# smarty09b.net
KiCad netlist of a schematic drawn in EAGLE
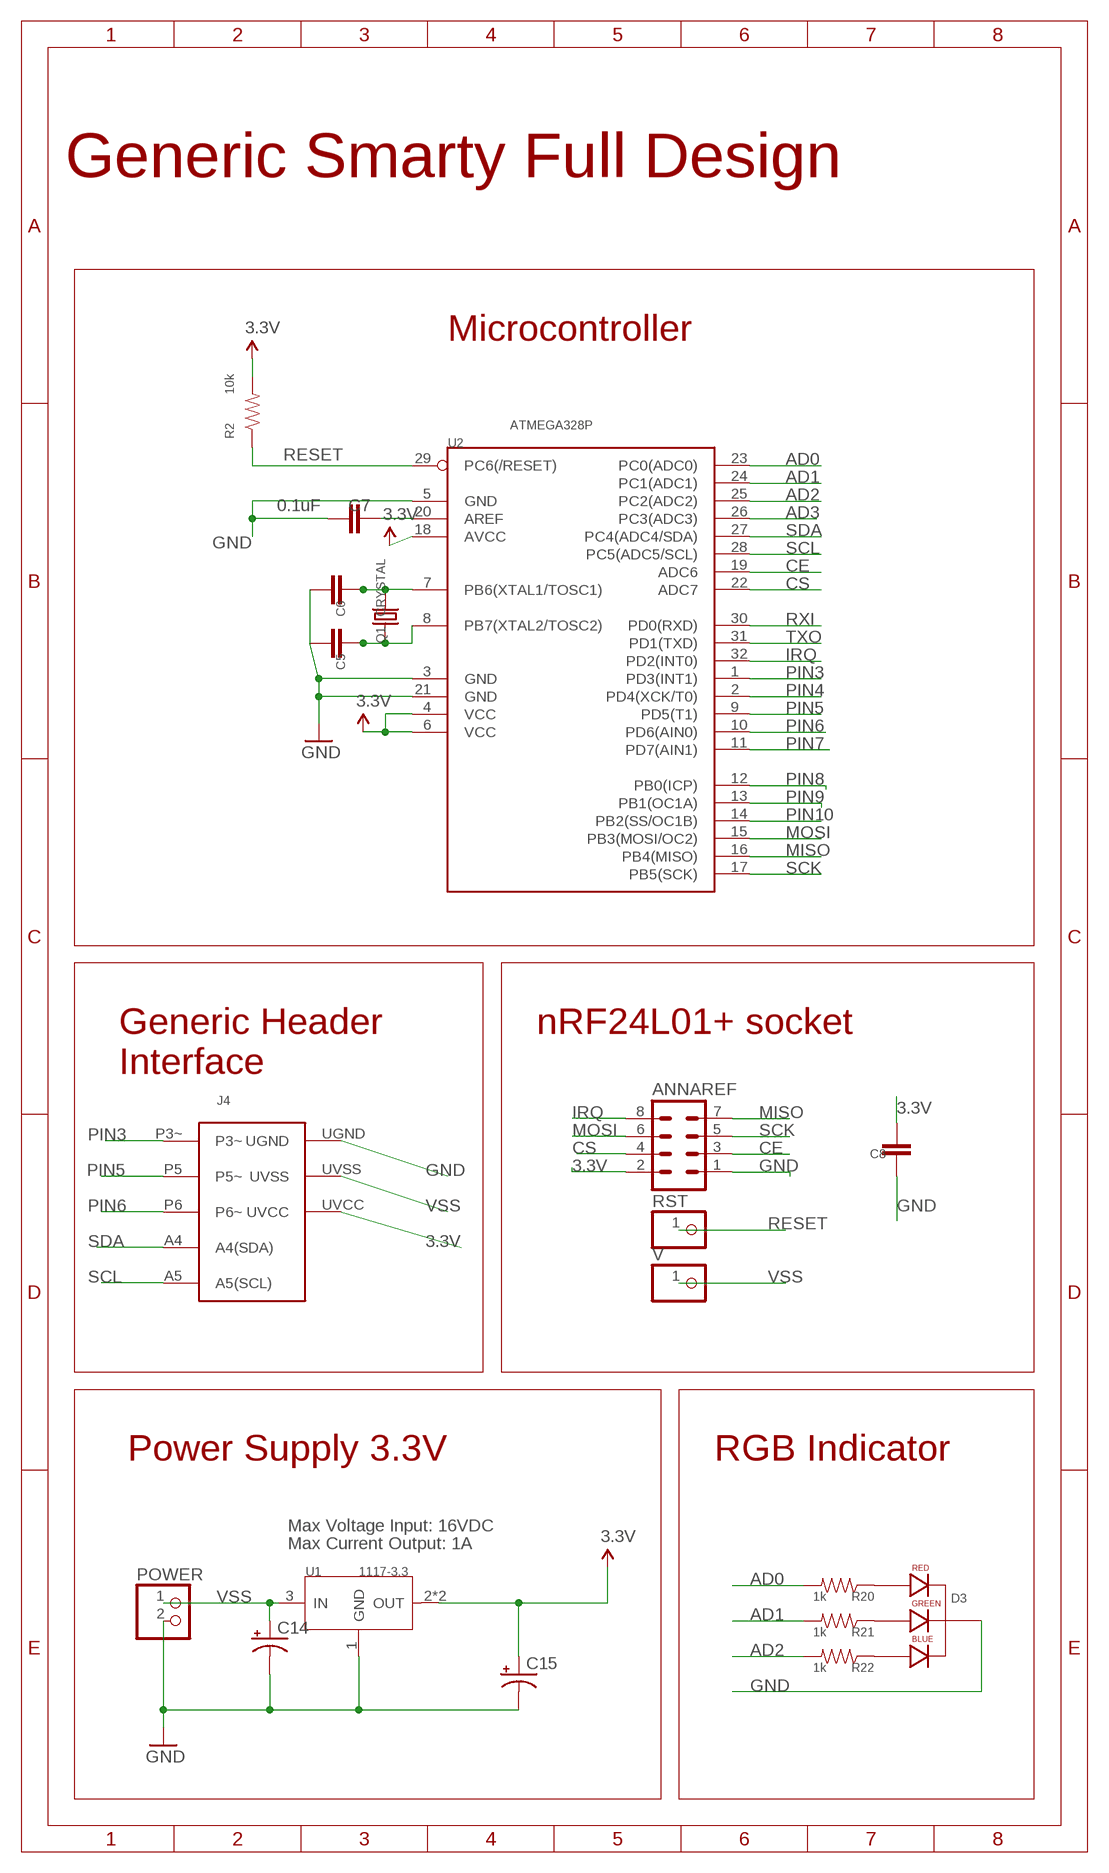
[diagram p0: schematic, sheet 1]

(export (version "E")
  (design (tool "Eeschema 10.0.6"))
  (components
    (comp (ref "ANNAREF")
      (value "MA04-2")
      (footprint "eagle-import:MA04-2")
      (libsource (lib "eagle-import") (part "MA04-2"))
    )
    (comp (ref "C5")
      (value "CAP1206")
      (footprint "eagle-import:1206")
      (libsource (lib "eagle-import") (part "CAP1206"))
    )
    (comp (ref "C6")
      (value "CAP1206")
      (footprint "eagle-import:1206")
      (libsource (lib "eagle-import") (part "CAP1206"))
    )
    (comp (ref "C7")
      (value "0.1uF")
      (footprint "eagle-import:1206")
      (libsource (lib "eagle-import") (part "CAP1206"))
    )
    (comp (ref "C8")
      (value "CAP1206")
      (footprint "eagle-import:1206")
      (libsource (lib "eagle-import") (part "CAP1206"))
    )
    (comp (ref "C14")
      (value "CAP_POL6032")
      (footprint "eagle-import:EIA6032")
      (libsource (lib "eagle-import") (part "CAP_POL6032"))
    )
    (comp (ref "C15")
      (value "CAP_POL6032")
      (footprint "eagle-import:EIA6032")
      (libsource (lib "eagle-import") (part "CAP_POL6032"))
    )
    (comp (ref "D3")
      (value "LED-RGB-CC-THRUCLEAR")
      (footprint "eagle-import:LED-RGB-THRU")
      (libsource (lib "eagle-import") (part "LED-RGB-CC-THRUCLEAR"))
    )
    (comp (ref "J4")
      (value "SMARTY-USHIELD")
      (footprint "eagle-import:SMARTY-USHIELD-2.54")
      (libsource (lib "eagle-import") (part "SMARTY-USHIELD"))
    )
    (comp (ref "POWER")
      (value "PINHD-1X2")
      (footprint "eagle-import:1X02")
      (libsource (lib "eagle-import") (part "PINHD-1X2"))
    )
    (comp (ref "Q1")
      (value "CRYSTAL")
      (footprint "eagle-import:2P-SMD-5.0X3.2")
      (libsource (lib "eagle-import") (part "CRYSTAL-0500290P1"))
    )
    (comp (ref "R2")
      (value "10k")
      (footprint "eagle-import:1206")
      (libsource (lib "eagle-import") (part "RESISTOR1206"))
    )
    (comp (ref "R20")
      (value "1k")
      (footprint "eagle-import:1206")
      (libsource (lib "eagle-import") (part "RESISTOR1206"))
    )
    (comp (ref "R21")
      (value "1k")
      (footprint "eagle-import:1206")
      (libsource (lib "eagle-import") (part "RESISTOR1206"))
    )
    (comp (ref "R22")
      (value "1k")
      (footprint "eagle-import:1206")
      (libsource (lib "eagle-import") (part "RESISTOR1206"))
    )
    (comp (ref "RST")
      (value "PINHD-1X1")
      (footprint "eagle-import:1X01")
      (libsource (lib "eagle-import") (part "PINHD-1X1"))
    )
    (comp (ref "U1")
      (value "1117-3.3")
      (footprint "eagle-import:SOT89")
      (libsource (lib "eagle-import") (part "CJ1117-3.3-1310120P1"))
    )
    (comp (ref "U2")
      (value "ATMEGA328P")
      (footprint "eagle-import:TQFP32")
      (libsource (lib "eagle-import") (part "ATMEGA328P-AU-1030060P1"))
    )
    (comp (ref "V")
      (value "PINHD-1X1")
      (footprint "eagle-import:1X01")
      (libsource (lib "eagle-import") (part "PINHD-1X1"))
    )
  )
  (nets
    (net (code "1") (name "/AD0") (class "Default")
      (node (ref "R20") (pin "2") (pinfunction "2_2") (pintype "passive"))
      (node (ref "U2") (pin "23") (pinfunction "PC0(ADC0)_23") (pintype "bidirectional"))
    )
    (net (code "2") (name "/AD1") (class "Default")
      (node (ref "R21") (pin "2") (pinfunction "2_2") (pintype "passive"))
      (node (ref "U2") (pin "24") (pinfunction "PC1(ADC1)_24") (pintype "bidirectional"))
    )
    (net (code "3") (name "/AD2") (class "Default")
      (node (ref "R22") (pin "2") (pinfunction "2_2") (pintype "passive"))
      (node (ref "U2") (pin "25") (pinfunction "PC2(ADC2)_25") (pintype "bidirectional"))
    )
    (net (code "4") (name "/AD3") (class "Default")
      (node (ref "U2") (pin "26") (pinfunction "PC3(ADC3)_26") (pintype "bidirectional"))
    )
    (net (code "5") (name "/CE") (class "Default")
      (node (ref "ANNAREF") (pin "3") (pinfunction "3_3") (pintype "passive"))
      (node (ref "U2") (pin "19") (pinfunction "ADC6_19") (pintype "bidirectional"))
    )
    (net (code "6") (name "/CS") (class "Default")
      (node (ref "ANNAREF") (pin "4") (pinfunction "4_4") (pintype "passive"))
      (node (ref "U2") (pin "22") (pinfunction "ADC7_22") (pintype "bidirectional"))
    )
    (net (code "7") (name "/IRQ") (class "Default")
      (node (ref "ANNAREF") (pin "8") (pinfunction "8_8") (pintype "passive"))
      (node (ref "U2") (pin "32") (pinfunction "PD2(INT0)_32") (pintype "bidirectional"))
    )
    (net (code "8") (name "/MISO") (class "Default")
      (node (ref "ANNAREF") (pin "7") (pinfunction "7_7") (pintype "passive"))
      (node (ref "U2") (pin "16") (pinfunction "PB4(MISO)_16") (pintype "bidirectional"))
    )
    (net (code "9") (name "/MOSI") (class "Default")
      (node (ref "ANNAREF") (pin "6") (pinfunction "6_6") (pintype "passive"))
      (node (ref "U2") (pin "15") (pinfunction "PB3(MOSI/OC2)_15") (pintype "bidirectional"))
    )
    (net (code "10") (name "/PIN3") (class "Default")
      (node (ref "J4") (pin "P3~") (pinfunction "P3~{}_P3~") (pintype "bidirectional"))
      (node (ref "U2") (pin "1") (pinfunction "PD3(INT1)_1") (pintype "bidirectional"))
    )
    (net (code "11") (name "/PIN4") (class "Default")
      (node (ref "U2") (pin "2") (pinfunction "PD4(XCK/T0)_2") (pintype "bidirectional"))
    )
    (net (code "12") (name "/PIN5") (class "Default")
      (node (ref "J4") (pin "P5") (pinfunction "P5~{}_P5") (pintype "bidirectional"))
      (node (ref "U2") (pin "9") (pinfunction "PD5(T1)_9") (pintype "bidirectional"))
    )
    (net (code "13") (name "/PIN6") (class "Default")
      (node (ref "J4") (pin "P6") (pinfunction "P6~{}_P6") (pintype "bidirectional"))
      (node (ref "U2") (pin "10") (pinfunction "PD6(AIN0)_10") (pintype "bidirectional"))
    )
    (net (code "14") (name "/PIN7") (class "Default")
      (node (ref "U2") (pin "11") (pinfunction "PD7(AIN1)_11") (pintype "bidirectional"))
    )
    (net (code "15") (name "/PIN8") (class "Default")
      (node (ref "U2") (pin "12") (pinfunction "PB0(ICP)_12") (pintype "bidirectional"))
    )
    (net (code "16") (name "/PIN9") (class "Default")
      (node (ref "U2") (pin "13") (pinfunction "PB1(OC1A)_13") (pintype "bidirectional"))
    )
    (net (code "17") (name "/PIN10") (class "Default")
      (node (ref "U2") (pin "14") (pinfunction "PB2(SS/OC1B)_14") (pintype "bidirectional"))
    )
    (net (code "18") (name "/RESET") (class "Default")
      (node (ref "R2") (pin "1") (pinfunction "1_1") (pintype "passive"))
      (node (ref "RST") (pin "1") (pinfunction "1_1") (pintype "passive"))
      (node (ref "U2") (pin "29") (pinfunction "PC6(/RESET)_29") (pintype "bidirectional"))
    )
    (net (code "19") (name "/RXI") (class "Default")
      (node (ref "U2") (pin "30") (pinfunction "PD0(RXD)_30") (pintype "bidirectional"))
    )
    (net (code "20") (name "/SCK") (class "Default")
      (node (ref "ANNAREF") (pin "5") (pinfunction "5_5") (pintype "passive"))
      (node (ref "U2") (pin "17") (pinfunction "PB5(SCK)_17") (pintype "bidirectional"))
    )
    (net (code "21") (name "/SCL") (class "Default")
      (node (ref "J4") (pin "A5") (pinfunction "A5(SCL)_A5") (pintype "bidirectional"))
      (node (ref "U2") (pin "28") (pinfunction "PC5(ADC5/SCL)_28") (pintype "bidirectional"))
    )
    (net (code "22") (name "/SDA") (class "Default")
      (node (ref "J4") (pin "A4") (pinfunction "A4(SDA)_A4") (pintype "bidirectional"))
      (node (ref "U2") (pin "27") (pinfunction "PC4(ADC4/SDA)_27") (pintype "bidirectional"))
    )
    (net (code "23") (name "/TXO") (class "Default")
      (node (ref "U2") (pin "31") (pinfunction "PD1(TXD)_31") (pintype "bidirectional"))
    )
    (net (code "24") (name "/VSS") (class "Default")
      (node (ref "C14") (pin "P$1") (pinfunction "+_P$1") (pintype "passive"))
      (node (ref "J4") (pin "UVSS") (pinfunction "UVSS_UVSS") (pintype "power_in"))
      (node (ref "POWER") (pin "1") (pinfunction "1_1") (pintype "passive"))
      (node (ref "U1") (pin "3") (pinfunction "IN_3") (pintype "bidirectional"))
      (node (ref "V") (pin "1") (pinfunction "1_1") (pintype "passive"))
    )
    (net (code "25") (name "3.3V") (class "Default")
      (node (ref "ANNAREF") (pin "2") (pinfunction "2_2") (pintype "passive"))
      (node (ref "C15") (pin "P$1") (pinfunction "+_P$1") (pintype "passive"))
      (node (ref "C8") (pin "1") (pinfunction "1_1") (pintype "passive"))
      (node (ref "J4") (pin "UVCC") (pinfunction "UVCC_UVCC") (pintype "power_in"))
      (node (ref "R2") (pin "2") (pinfunction "2_2") (pintype "passive"))
      (node (ref "U1") (pin "2") (pinfunction "OUT_2") (pintype "bidirectional"))
      (node (ref "U1") (pin "4") (pinfunction "OUT_4") (pintype "bidirectional"))
      (node (ref "U2") (pin "18") (pinfunction "AVCC_18") (pintype "bidirectional"))
      (node (ref "U2") (pin "4") (pinfunction "VCC_4") (pintype "bidirectional"))
      (node (ref "U2") (pin "6") (pinfunction "VCC_6") (pintype "bidirectional"))
    )
    (net (code "26") (name "GND") (class "Default")
      (node (ref "ANNAREF") (pin "1") (pinfunction "1_1") (pintype "passive"))
      (node (ref "C14") (pin "P$2") (pinfunction "-_P$2") (pintype "passive"))
      (node (ref "C15") (pin "P$2") (pinfunction "-_P$2") (pintype "passive"))
      (node (ref "C5") (pin "1") (pinfunction "1_1") (pintype "passive"))
      (node (ref "C6") (pin "1") (pinfunction "1_1") (pintype "passive"))
      (node (ref "C7") (pin "2") (pinfunction "2_2") (pintype "passive"))
      (node (ref "C8") (pin "2") (pinfunction "2_2") (pintype "passive"))
      (node (ref "D3") (pin "2") (pinfunction "CATHODE_2") (pintype "bidirectional"))
      (node (ref "J4") (pin "UGND") (pinfunction "UGND_UGND") (pintype "power_in"))
      (node (ref "POWER") (pin "2") (pinfunction "2_2") (pintype "passive"))
      (node (ref "U1") (pin "1") (pinfunction "GND_1") (pintype "bidirectional"))
      (node (ref "U2") (pin "21") (pinfunction "GND_21") (pintype "bidirectional"))
      (node (ref "U2") (pin "3") (pinfunction "GND_3") (pintype "bidirectional"))
      (node (ref "U2") (pin "5") (pinfunction "GND_5") (pintype "bidirectional"))
    )
    (net (code "27") (name "Net-(D3-BLUE_CATHODE)") (class "Default")
      (node (ref "D3") (pin "4") (pinfunction "BLUE_CATHODE_4") (pintype "bidirectional"))
      (node (ref "R22") (pin "1") (pinfunction "1_1") (pintype "passive"))
    )
    (net (code "28") (name "Net-(D3-GREEN_CATHODE)") (class "Default")
      (node (ref "D3") (pin "3") (pinfunction "GREEN_CATHODE_3") (pintype "bidirectional"))
      (node (ref "R21") (pin "1") (pinfunction "1_1") (pintype "passive"))
    )
    (net (code "29") (name "Net-(D3-RED_CATHODE)") (class "Default")
      (node (ref "D3") (pin "1") (pinfunction "RED_CATHODE_1") (pintype "bidirectional"))
      (node (ref "R20") (pin "1") (pinfunction "1_1") (pintype "passive"))
    )
    (net (code "30") (name "Net-(U2-AREF)") (class "Default")
      (node (ref "C7") (pin "1") (pinfunction "1_1") (pintype "passive"))
      (node (ref "U2") (pin "20") (pinfunction "AREF_20") (pintype "bidirectional"))
    )
    (net (code "31") (name "Net-(U2-PB6(XTAL1{slash}TOSC1))") (class "Default")
      (node (ref "C6") (pin "2") (pinfunction "2_2") (pintype "passive"))
      (node (ref "Q1") (pin "2") (pinfunction "2_2") (pintype "passive"))
      (node (ref "U2") (pin "7") (pinfunction "PB6(XTAL1/TOSC1)_7") (pintype "bidirectional"))
    )
    (net (code "32") (name "Net-(U2-PB7(XTAL2{slash}TOSC2))") (class "Default")
      (node (ref "C5") (pin "2") (pinfunction "2_2") (pintype "passive"))
      (node (ref "Q1") (pin "1") (pinfunction "1_1") (pintype "passive"))
      (node (ref "U2") (pin "8") (pinfunction "PB7(XTAL2/TOSC2)_8") (pintype "bidirectional"))
    )
  )
)
